# ThermocoupleBreakoutBoard.net
KiCad netlist of a schematic drawn in EAGLE
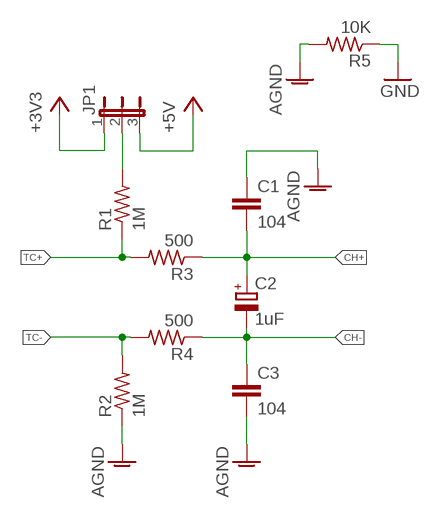
[diagram p0: schematic, sheet 1]

(export (version "E")
  (design (tool "Eeschema 10.0.6"))
  (components
    (comp (ref "C1")
      (value "104")
      (footprint "eagle-import:C1206")
      (libsource (lib "eagle-import") (part "C-EUC1206"))
    )
    (comp (ref "C2")
      (value "1uF")
      (footprint "eagle-import:E2,5-6")
      (libsource (lib "eagle-import") (part "CPOL-EUE2.5-6"))
    )
    (comp (ref "C3")
      (value "104")
      (footprint "eagle-import:C1206")
      (libsource (lib "eagle-import") (part "C-EUC1206"))
    )
    (comp (ref "JP1")
      (value "JP2E")
      (footprint "eagle-import:JP2")
      (libsource (lib "eagle-import") (part "JP2E"))
    )
    (comp (ref "R1")
      (value "1M")
      (footprint "eagle-import:M1206")
      (libsource (lib "eagle-import") (part "R-US_M1206"))
    )
    (comp (ref "R2")
      (value "1M")
      (footprint "eagle-import:M1206")
      (libsource (lib "eagle-import") (part "R-US_M1206"))
    )
    (comp (ref "R3")
      (value "500")
      (footprint "eagle-import:M1206")
      (libsource (lib "eagle-import") (part "R-US_M1206"))
    )
    (comp (ref "R4")
      (value "500")
      (footprint "eagle-import:M1206")
      (libsource (lib "eagle-import") (part "R-US_M1206"))
    )
    (comp (ref "R5")
      (value "10K")
      (footprint "eagle-import:M1206")
      (libsource (lib "eagle-import") (part "R-US_M1206"))
    )
  )
  (nets
    (net (code "1") (name "+3V3") (class "Default")
      (node (ref "JP1") (pin "1") (pinfunction "1_1") (pintype "passive"))
    )
    (net (code "2") (name "+5V") (class "Default")
      (node (ref "JP1") (pin "3") (pinfunction "3_3") (pintype "passive"))
    )
    (net (code "3") (name "AGND") (class "Default")
      (node (ref "C1") (pin "1") (pinfunction "1_1") (pintype "passive"))
      (node (ref "C3") (pin "2") (pinfunction "2_2") (pintype "passive"))
      (node (ref "R2") (pin "1") (pinfunction "1_1") (pintype "passive"))
      (node (ref "R5") (pin "2") (pinfunction "2_2") (pintype "passive"))
    )
    (net (code "4") (name "CH+") (class "Default")
      (node (ref "C1") (pin "2") (pinfunction "2_2") (pintype "passive"))
      (node (ref "C2") (pin "+") (pinfunction "+_+") (pintype "passive"))
      (node (ref "R3") (pin "1") (pinfunction "1_1") (pintype "passive"))
    )
    (net (code "5") (name "CH-") (class "Default")
      (node (ref "C2") (pin "-") (pinfunction "-_-") (pintype "passive"))
      (node (ref "C3") (pin "1") (pinfunction "1_1") (pintype "passive"))
      (node (ref "R4") (pin "1") (pinfunction "1_1") (pintype "passive"))
    )
    (net (code "6") (name "GND") (class "Default")
      (node (ref "R5") (pin "1") (pinfunction "1_1") (pintype "passive"))
    )
    (net (code "7") (name "Net-(JP1-Pad2)") (class "Default")
      (node (ref "JP1") (pin "2") (pinfunction "2_2") (pintype "passive"))
      (node (ref "R1") (pin "2") (pinfunction "2_2") (pintype "passive"))
    )
    (net (code "8") (name "TC+") (class "Default")
      (node (ref "R1") (pin "1") (pinfunction "1_1") (pintype "passive"))
      (node (ref "R3") (pin "2") (pinfunction "2_2") (pintype "passive"))
    )
    (net (code "9") (name "TC-") (class "Default")
      (node (ref "R2") (pin "2") (pinfunction "2_2") (pintype "passive"))
      (node (ref "R4") (pin "2") (pinfunction "2_2") (pintype "passive"))
    )
  )
)
